# latest_schematic.net
KiCad netlist of a schematic drawn in EasyEDA
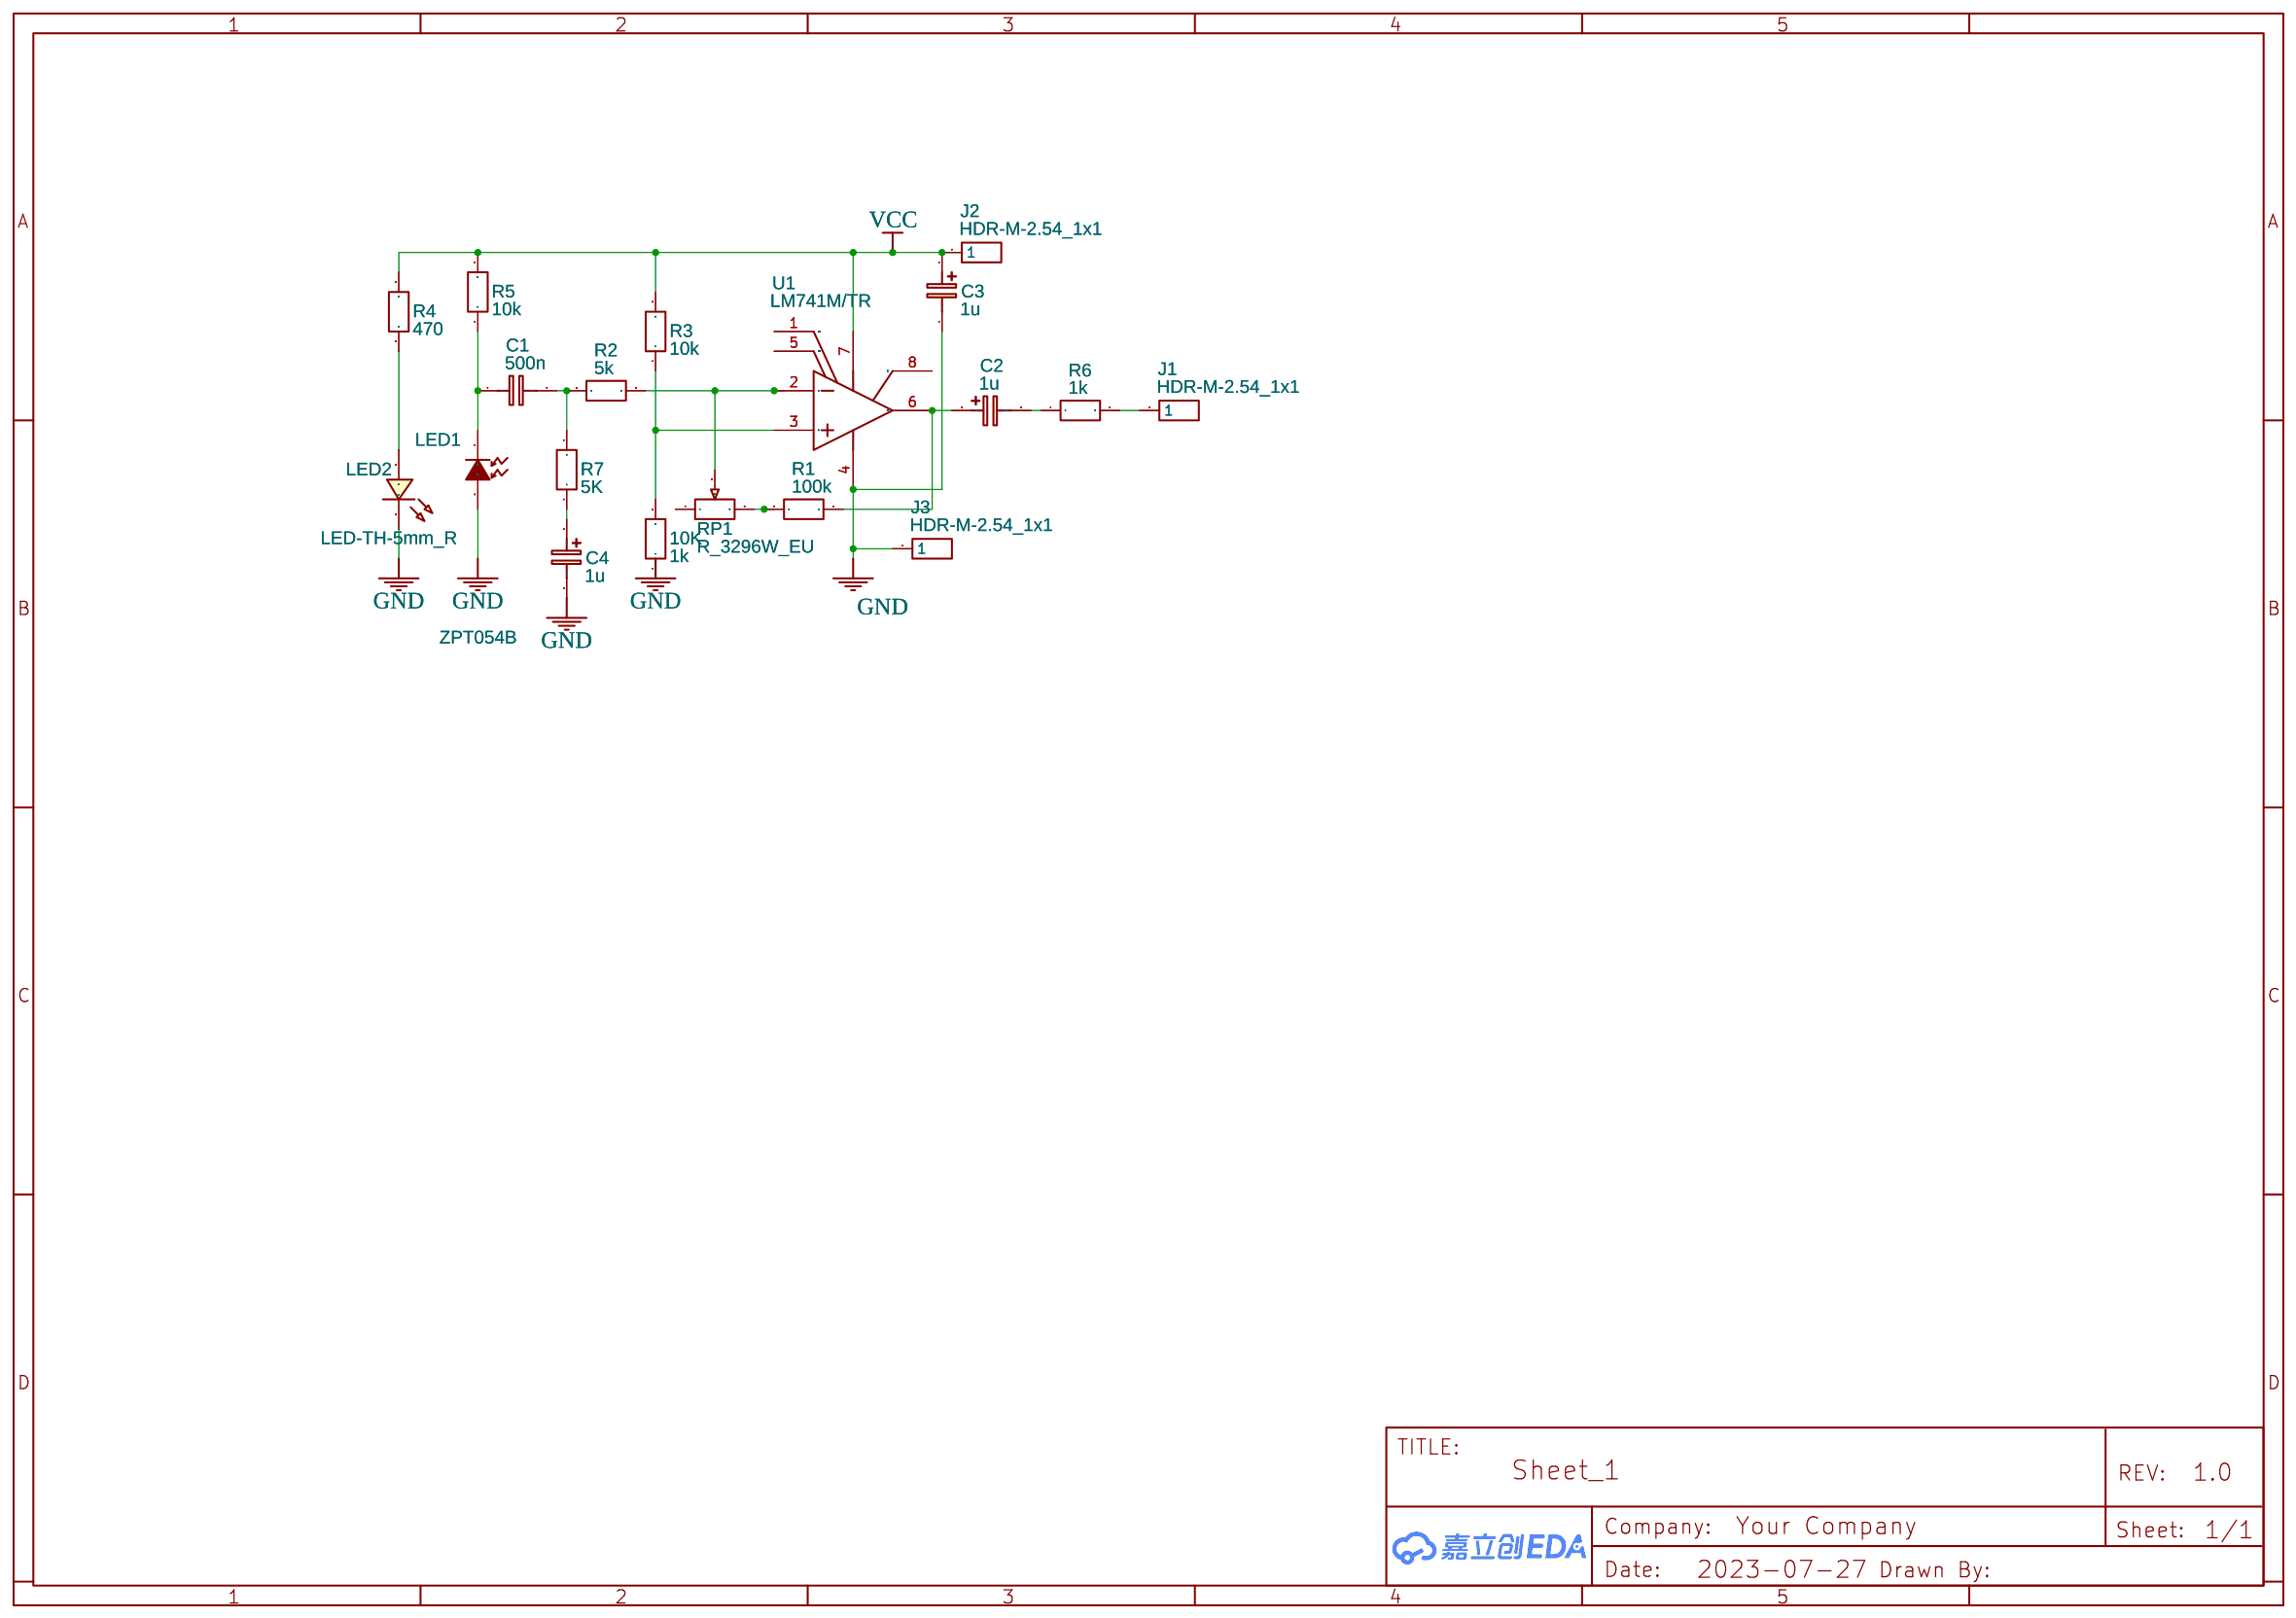
[diagram p0: schematic sheet]

(export (version "E")
  (design (tool "Eeschema 10.0.6"))
  (components
    (comp (ref "10K") (value "1k") (libsource (lib "") (part "R_0603_EU_2")))
    (comp (ref "C1") (value "500n") (libsource (lib "") (part "C_0603_EU")))
    (comp (ref "C2") (value "1u") (libsource (lib "") (part "C_Tan_SMD_A_EU")))
    (comp (ref "C3") (value "1u") (libsource (lib "") (part "C_Tan_SMD_A_EU_1")))
    (comp (ref "C4") (value "1u") (libsource (lib "") (part "C_Tan_SMD_A_EU_1")))
    (comp (ref "J1")
      (value "HDR-M-2.54_1x1")
      (fields (field (name "BOM_Supplier Part") "C81276"))
      (libsource (lib "") (part "HDR-M-2.54_1x1"))
    )
    (comp (ref "J2")
      (value "HDR-M-2.54_1x1")
      (fields (field (name "BOM_Supplier Part") "C81276"))
      (libsource (lib "") (part "HDR-M-2.54_1x1"))
    )
    (comp (ref "J3")
      (value "HDR-M-2.54_1x1")
      (fields (field (name "BOM_Supplier Part") "C81276"))
      (libsource (lib "") (part "HDR-M-2.54_1x1"))
    )
    (comp (ref "LED1")
      (value "ZPT054B")
      (fields (field (name "Manufacturer") "Chau Light"))
      (libsource (lib "") (part "ZPT054B"))
    )
    (comp (ref "LED2")
      (value "LED-TH-5mm_R")
      (fields
        (field (name "BOM_Manufacturer Part") "333-2SURD/S530-A3")
        (field (name "BOM_Supplier Part") "C87271")
      )
      (libsource (lib "") (part "LED-TH-5mm_R"))
    )
    (comp (ref "R1") (value "100k") (libsource (lib "") (part "R_0603_EU_1")))
    (comp (ref "R2") (value "5k") (libsource (lib "") (part "R_0603_EU_1")))
    (comp (ref "R3") (value "10k") (libsource (lib "") (part "R_0603_EU")))
    (comp (ref "R4") (value "470") (libsource (lib "") (part "R_0603_EU")))
    (comp (ref "R5") (value "10k") (libsource (lib "") (part "R_0603_EU")))
    (comp (ref "R6") (value "1k") (libsource (lib "") (part "R_0603_EU_1")))
    (comp (ref "R7") (value "5K") (libsource (lib "") (part "R_0603_EU")))
    (comp (ref "RP1") (value "R_3296W_EU") (libsource (lib "") (part "R_3296W_EU")))
    (comp (ref "U1")
      (value "LM741M/TR")
      (fields (field (name "Manufacturer") "HGSEMI(华冠)"))
      (libsource (lib "") (part "LM741M/TR"))
    )
  )
  (nets
    (net (code "1") (name "GND") (class "Default")
      (node (ref "10K") (pin "1") (pinfunction "1_1") (pintype "unspecified"))
      (node (ref "C3") (pin "2") (pinfunction "2_2") (pintype "unspecified"))
      (node (ref "C4") (pin "2") (pinfunction "2_2") (pintype "unspecified"))
      (node (ref "J3") (pin "1") (pinfunction "1_1") (pintype "input"))
      (node (ref "LED1") (pin "2") (pinfunction "C_2") (pintype "input"))
      (node (ref "LED2") (pin "2") (pinfunction "2_2") (pintype "unspecified"))
      (node (ref "U1") (pin "4") (pinfunction "V-_4") (pintype "passive"))
    )
    (net (code "2") (name "Net-(C1-Pad2)") (class "Default")
      (node (ref "C1") (pin "2") (pinfunction "2_2") (pintype "unspecified"))
      (node (ref "R2") (pin "1") (pinfunction "1_1") (pintype "unspecified"))
      (node (ref "R7") (pin "2") (pinfunction "2_2") (pintype "unspecified"))
    )
    (net (code "3") (name "Net-(C2-Pad2)") (class "Default")
      (node (ref "C2") (pin "2") (pinfunction "2_2") (pintype "unspecified"))
      (node (ref "R6") (pin "1") (pinfunction "1_1") (pintype "unspecified"))
    )
    (net (code "4") (name "Net-(C4-Pad1)") (class "Default")
      (node (ref "C4") (pin "1") (pinfunction "1_1") (pintype "unspecified"))
      (node (ref "R7") (pin "1") (pinfunction "1_1") (pintype "unspecified"))
    )
    (net (code "5") (name "Net-(J1-Pad1)") (class "Default")
      (node (ref "J1") (pin "1") (pinfunction "1_1") (pintype "input"))
      (node (ref "R6") (pin "2") (pinfunction "2_2") (pintype "unspecified"))
    )
    (net (code "6") (name "Net-(LED1-E)") (class "Default")
      (node (ref "C1") (pin "1") (pinfunction "1_1") (pintype "unspecified"))
      (node (ref "LED1") (pin "1") (pinfunction "E_1") (pintype "input"))
      (node (ref "R5") (pin "1") (pinfunction "1_1") (pintype "unspecified"))
    )
    (net (code "7") (name "Net-(LED2-Pad1)") (class "Default")
      (node (ref "LED2") (pin "1") (pinfunction "1_1") (pintype "unspecified"))
      (node (ref "R4") (pin "1") (pinfunction "1_1") (pintype "unspecified"))
    )
    (net (code "8") (name "Net-(R1-Pad1)") (class "Default")
      (node (ref "R1") (pin "1") (pinfunction "1_1") (pintype "unspecified"))
      (node (ref "RP1") (pin "3") (pinfunction "3_3") (pintype "input"))
    )
    (net (code "9") (name "Net-(U1-IN+)") (class "Default")
      (node (ref "10K") (pin "2") (pinfunction "2_2") (pintype "unspecified"))
      (node (ref "R3") (pin "1") (pinfunction "1_1") (pintype "unspecified"))
      (node (ref "U1") (pin "3") (pinfunction "IN+_3") (pintype "unspecified"))
    )
    (net (code "10") (name "Net-(U1-IN-)") (class "Default")
      (node (ref "R2") (pin "2") (pinfunction "2_2") (pintype "unspecified"))
      (node (ref "RP1") (pin "2") (pinfunction "2_2") (pintype "input"))
      (node (ref "U1") (pin "2") (pinfunction "IN-_2") (pintype "unspecified"))
    )
    (net (code "11") (name "Net-(U1-OUT)") (class "Default")
      (node (ref "C2") (pin "1") (pinfunction "1_1") (pintype "unspecified"))
      (node (ref "R1") (pin "2") (pinfunction "2_2") (pintype "unspecified"))
      (node (ref "U1") (pin "6") (pinfunction "OUT_6") (pintype "output"))
    )
    (net (code "12") (name "VCC") (class "Default")
      (node (ref "C3") (pin "1") (pinfunction "1_1") (pintype "unspecified"))
      (node (ref "J2") (pin "1") (pinfunction "1_1") (pintype "input"))
      (node (ref "R3") (pin "2") (pinfunction "2_2") (pintype "unspecified"))
      (node (ref "R4") (pin "2") (pinfunction "2_2") (pintype "unspecified"))
      (node (ref "R5") (pin "2") (pinfunction "2_2") (pintype "unspecified"))
      (node (ref "U1") (pin "7") (pinfunction "V+_7") (pintype "passive"))
    )
    (net (code "13") (name "unconnected-(RP1-Pad1)") (class "Default")
      (node (ref "RP1") (pin "1") (pinfunction "1_1") (pintype "input"))
    )
    (net (code "14") (name "unconnected-(U1-NC-Pad8)") (class "Default")
      (node (ref "U1") (pin "8") (pinfunction "NC_8") (pintype "unspecified"))
    )
    (net (code "15") (name "unconnected-(U1-OFFSET_NULL-Pad1)") (class "Default")
      (node (ref "U1") (pin "1") (pinfunction "OFFSET_NULL_1") (pintype "unspecified"))
    )
    (net (code "16") (name "unconnected-(U1-OFFSET_NULL-Pad5)") (class "Default")
      (node (ref "U1") (pin "5") (pinfunction "OFFSET_NULL_5") (pintype "unspecified"))
    )
  )
)
